# Sheet1.net
KiCad netlist of a schematic drawn in Altium Designer
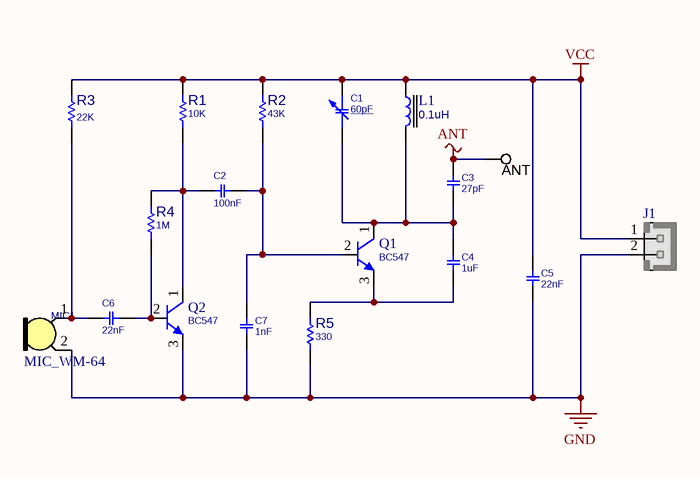
[diagram p0: Sheet1.SchDoc]

(export (version "E")
  (design (tool "Eeschema 10.0.6"))
  (components
    (comp (ref "ANT")
      (value "TESTPOINT_MINI")
      (footprint "TPTHD_A")
      (description "TEST POINT")
      (fields (field (name "MANF") "MANF") (field (name "MANF_P#") "MANF_P#"))
      (libsource (lib "test-tp_jumper") (part "TESTPOINT_MINI"))
    )
    (comp (ref "C1")
      (value "60pF")
      (footprint "CTRM_6X6")
      (description "CAP, THD, TRIMMER")
      (fields (field (name "MANF_P#") "MANF_PART#") (field (name "MANF") "MANF"))
      (libsource (lib "passive_thd") (part "CAP_THD_TRIMMER"))
    )
    (comp (ref "C2")
      (value "100nF")
      (footprint "C_CERM_D3")
      (description "CAP, THD, CER MULTI LAYER,")
      (fields (field (name "MANF_P#") "MANF_PART#") (field (name "MANF") "MANF"))
      (libsource (lib "passive_thd") (part "CAP_THD_CER"))
    )
    (comp (ref "C3")
      (value "27pF")
      (footprint "C_CERM_D3")
      (description "CAP, THD, CER MULTI LAYER,")
      (fields (field (name "MANF_P#") "MANF_PART#") (field (name "MANF") "MANF"))
      (libsource (lib "passive_thd") (part "CAP_THD_CER"))
    )
    (comp (ref "C4")
      (value "1uF")
      (footprint "C_CERM_D3")
      (description "CAP, THD, CER MULTI LAYER,")
      (fields (field (name "MANF_P#") "MANF_PART#") (field (name "MANF") "MANF"))
      (libsource (lib "passive_thd") (part "CAP_THD_CER"))
    )
    (comp (ref "C5")
      (value "22nF")
      (footprint "C_CERM_D3")
      (description "CAP, THD, CER MULTI LAYER,")
      (fields (field (name "MANF_P#") "MANF_PART#") (field (name "MANF") "MANF"))
      (libsource (lib "passive_thd") (part "CAP_THD_CER"))
    )
    (comp (ref "C6")
      (value "22nF")
      (footprint "C_CERM_D3")
      (description "CAP, THD, CER MULTI LAYER,")
      (fields (field (name "MANF_P#") "MANF_PART#") (field (name "MANF") "MANF"))
      (libsource (lib "passive_thd") (part "CAP_THD_CER"))
    )
    (comp (ref "C7")
      (value "1nF")
      (footprint "C_CERM_D3")
      (description "CAP, THD, CER MULTI LAYER,")
      (fields (field (name "MANF_P#") "MANF_PART#") (field (name "MANF") "MANF"))
      (libsource (lib "passive_thd") (part "CAP_THD_CER"))
    )
    (comp (ref "J1")
      (value "HHDR_2")
      (footprint "XH_2")
      (description "JST-XH pitch: 2.5mm")
      (libsource (lib "conn_wire2board") (part "XH_2"))
    )
    (comp (ref "L1")
      (value "0.1uH")
      (footprint "LT_AX025")
      (description "INDUCTOR, THD")
      (libsource (lib "passive_thd") (part "IND_THD"))
    )
    (comp (ref "MIC1")
      (value "MIC_WM-64")
      (footprint "MIC_C6")
      (description "MICROPHONE OMNI 6X2.2MM W/CAP 2.2KOHM -44DB TH")
      (fields (field (name "MANF_P#") "WM-64PNT"))
      (libsource (lib "audio_mic_spk") (part "MIC_WM-64"))
    )
    (comp (ref "Q1")
      (value "BC547")
      (footprint "TO92_3")
      (description "BJT, NPN, 45v, 0.1A, THD, TO92")
      (fields (field (name "MANF") "FAIRCHILD"))
      (libsource (lib "transistor_bjt") (part "NPN_BC547_TO92"))
    )
    (comp (ref "Q2")
      (value "BC547")
      (footprint "TO92_3")
      (description "BJT, NPN, 45v, 0.1A, THD, TO92")
      (fields (field (name "MANF") "FAIRCHILD"))
      (libsource (lib "transistor_bjt") (part "NPN_BC547_TO92"))
    )
    (comp (ref "R1")
      (value "10K")
      (footprint "R025W_AX04")
      (description "RESISTOR, THD")
      (fields (field (name "MANF_P#") "RK73H1ETTP4701F") (field (name "MANF") "KOA SPEER"))
      (libsource (lib "passive_thd") (part "RES_THD"))
    )
    (comp (ref "R2")
      (value "43K")
      (footprint "R025W_AX04")
      (description "RESISTOR, THD")
      (fields (field (name "MANF_P#") "RK73H1ETTP4701F") (field (name "MANF") "KOA SPEER"))
      (libsource (lib "passive_thd") (part "RES_THD"))
    )
    (comp (ref "R3")
      (value "22K")
      (footprint "R025W_AX04")
      (description "RESISTOR, THD")
      (fields (field (name "MANF_P#") "RK73H1ETTP4701F") (field (name "MANF") "KOA SPEER"))
      (libsource (lib "passive_thd") (part "RES_THD"))
    )
    (comp (ref "R4")
      (value "1M")
      (footprint "R025W_AX04")
      (description "RESISTOR, THD")
      (fields (field (name "MANF_P#") "RK73H1ETTP4701F") (field (name "MANF") "KOA SPEER"))
      (libsource (lib "passive_thd") (part "RES_THD"))
    )
    (comp (ref "R5")
      (value "330")
      (footprint "R025W_AX04")
      (description "RESISTOR, THD")
      (fields (field (name "MANF_P#") "RK73H1ETTP4701F") (field (name "MANF") "KOA SPEER"))
      (libsource (lib "passive_thd") (part "RES_THD"))
    )
  )
  (nets
    (net (code "1") (name "ANT") (class "Default")
      (node (ref "ANT") (pin "1") (pinfunction "1_1") (pintype "passive"))
      (node (ref "C3") (pin "1") (pinfunction "1_1") (pintype "passive"))
    )
    (net (code "2") (name "GND") (class "Default")
      (node (ref "C5") (pin "2") (pinfunction "2_2") (pintype "passive"))
      (node (ref "C7") (pin "1") (pinfunction "1_1") (pintype "passive"))
      (node (ref "J1") (pin "2") (pinfunction "2_2") (pintype "passive"))
      (node (ref "MIC1") (pin "2") (pinfunction "GND_2") (pintype "passive"))
      (node (ref "Q2") (pin "3") (pinfunction "E_3") (pintype "passive"))
      (node (ref "R5") (pin "1") (pinfunction "1_1") (pintype "passive"))
    )
    (net (code "3") (name "Net-(MIC1-OUT)") (class "Default")
      (node (ref "C6") (pin "2") (pinfunction "2_2") (pintype "passive"))
      (node (ref "MIC1") (pin "1") (pinfunction "OUT_1") (pintype "passive"))
      (node (ref "R3") (pin "1") (pinfunction "1_1") (pintype "passive"))
    )
    (net (code "4") (name "Net-(Q1-B)") (class "Default")
      (node (ref "C2") (pin "1") (pinfunction "1_1") (pintype "passive"))
      (node (ref "C7") (pin "2") (pinfunction "2_2") (pintype "passive"))
      (node (ref "Q1") (pin "2") (pinfunction "B_2") (pintype "passive"))
      (node (ref "R2") (pin "1") (pinfunction "1_1") (pintype "passive"))
    )
    (net (code "5") (name "Net-(Q1-C)") (class "Default")
      (node (ref "C1") (pin "1") (pinfunction "1_1") (pintype "passive"))
      (node (ref "C3") (pin "2") (pinfunction "2_2") (pintype "passive"))
      (node (ref "C4") (pin "1") (pinfunction "1_1") (pintype "passive"))
      (node (ref "L1") (pin "2") (pinfunction "2_2") (pintype "passive"))
      (node (ref "Q1") (pin "1") (pinfunction "C_1") (pintype "passive"))
    )
    (net (code "6") (name "Net-(Q1-E)") (class "Default")
      (node (ref "C4") (pin "2") (pinfunction "2_2") (pintype "passive"))
      (node (ref "Q1") (pin "3") (pinfunction "E_3") (pintype "passive"))
      (node (ref "R5") (pin "2") (pinfunction "2_2") (pintype "passive"))
    )
    (net (code "7") (name "Net-(Q2-B)") (class "Default")
      (node (ref "C6") (pin "1") (pinfunction "1_1") (pintype "passive"))
      (node (ref "Q2") (pin "2") (pinfunction "B_2") (pintype "passive"))
      (node (ref "R4") (pin "1") (pinfunction "1_1") (pintype "passive"))
    )
    (net (code "8") (name "Net-(Q2-C)") (class "Default")
      (node (ref "C2") (pin "2") (pinfunction "2_2") (pintype "passive"))
      (node (ref "Q2") (pin "1") (pinfunction "C_1") (pintype "passive"))
      (node (ref "R1") (pin "1") (pinfunction "1_1") (pintype "passive"))
      (node (ref "R4") (pin "2") (pinfunction "2_2") (pintype "passive"))
    )
    (net (code "9") (name "VCC") (class "Default")
      (node (ref "C1") (pin "2") (pinfunction "2_2") (pintype "passive"))
      (node (ref "C5") (pin "1") (pinfunction "1_1") (pintype "passive"))
      (node (ref "J1") (pin "1") (pinfunction "1_1") (pintype "passive"))
      (node (ref "L1") (pin "1") (pinfunction "1_1") (pintype "passive"))
      (node (ref "R1") (pin "2") (pinfunction "2_2") (pintype "passive"))
      (node (ref "R2") (pin "2") (pinfunction "2_2") (pintype "passive"))
      (node (ref "R3") (pin "2") (pinfunction "2_2") (pintype "passive"))
    )
  )
)
